# SmartCar_ESP_V2.net
KiCad netlist of a schematic drawn in EAGLE
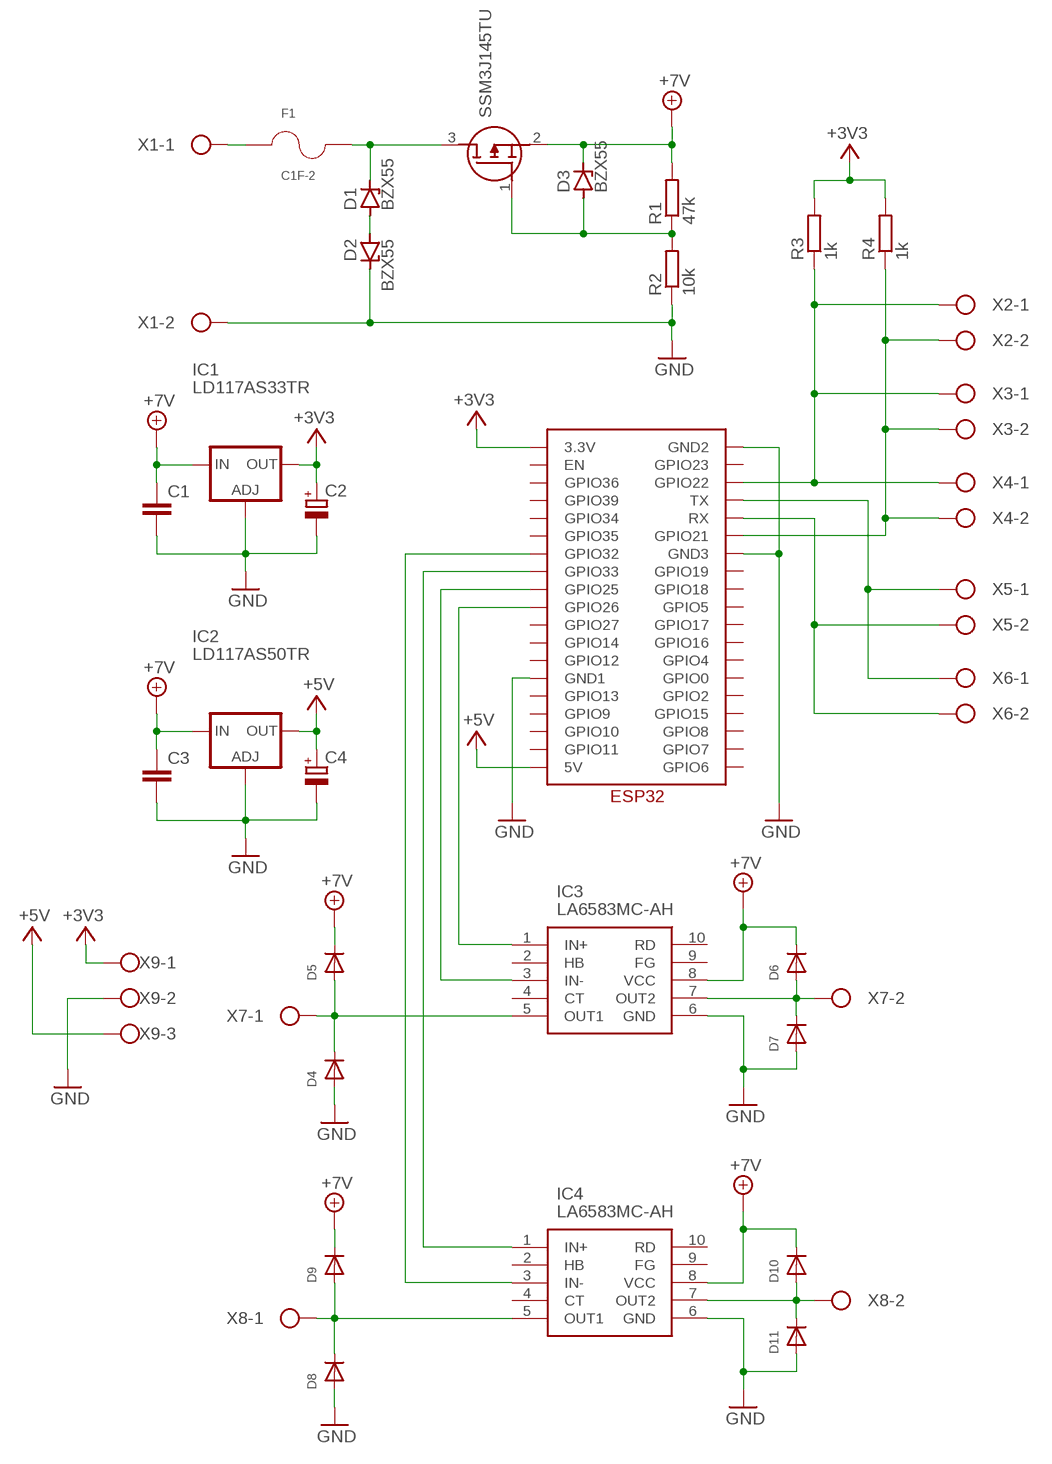
[diagram p0: schematic, sheet 1]

(export (version "E")
  (design (tool "Eeschema 10.0.6"))
  (components
    (comp (ref "C1")
      (value "C-EUC0805")
      (footprint "eagle-import:C0805")
      (libsource (lib "eagle-import") (part "C-EUC0805"))
    )
    (comp (ref "C2")
      (value "CPOL-EUE2,5-6E")
      (footprint "eagle-import:E2,5-6E")
      (libsource (lib "eagle-import") (part "CPOL-EUE2,5-6E"))
    )
    (comp (ref "C3")
      (value "C-EUC0805")
      (footprint "eagle-import:C0805")
      (libsource (lib "eagle-import") (part "C-EUC0805"))
    )
    (comp (ref "C4")
      (value "CPOL-EUE2,5-6E")
      (footprint "eagle-import:E2,5-6E")
      (libsource (lib "eagle-import") (part "CPOL-EUE2,5-6E"))
    )
    (comp (ref "D1")
      (value "BZX55")
      (footprint "eagle-import:DO35Z10")
      (libsource (lib "eagle-import") (part "BZX55"))
    )
    (comp (ref "D2")
      (value "BZX55")
      (footprint "eagle-import:DO35Z10")
      (libsource (lib "eagle-import") (part "BZX55"))
    )
    (comp (ref "D3")
      (value "BZX55")
      (footprint "eagle-import:DO35Z10")
      (libsource (lib "eagle-import") (part "BZX55"))
    )
    (comp (ref "D4")
      (value "DIODESMA")
      (footprint "eagle-import:SMADIODE")
      (libsource (lib "eagle-import") (part "DIODESMA"))
    )
    (comp (ref "D5")
      (value "DIODESMA")
      (footprint "eagle-import:SMADIODE")
      (libsource (lib "eagle-import") (part "DIODESMA"))
    )
    (comp (ref "D6")
      (value "DIODESMA")
      (footprint "eagle-import:SMADIODE")
      (libsource (lib "eagle-import") (part "DIODESMA"))
    )
    (comp (ref "D7")
      (value "DIODESMA")
      (footprint "eagle-import:SMADIODE")
      (libsource (lib "eagle-import") (part "DIODESMA"))
    )
    (comp (ref "D8")
      (value "DIODESMA")
      (footprint "eagle-import:SMADIODE")
      (libsource (lib "eagle-import") (part "DIODESMA"))
    )
    (comp (ref "D9")
      (value "DIODESMA")
      (footprint "eagle-import:SMADIODE")
      (libsource (lib "eagle-import") (part "DIODESMA"))
    )
    (comp (ref "D10")
      (value "DIODESMA")
      (footprint "eagle-import:SMADIODE")
      (libsource (lib "eagle-import") (part "DIODESMA"))
    )
    (comp (ref "D11")
      (value "DIODESMA")
      (footprint "eagle-import:SMADIODE")
      (libsource (lib "eagle-import") (part "DIODESMA"))
    )
    (comp (ref "F1")
      (value "C1F-2")
      (footprint "eagle-import:FUSC3215X83N")
      (fields (field (name "MANUFACTURER") "Bel Fuse Inc."))
      (libsource (lib "eagle-import") (part "C1F-2"))
    )
    (comp (ref "IC1")
      (value "LD117AS33TR")
      (footprint "eagle-import:SOT223")
      (libsource (lib "eagle-import") (part "LD117A?S33TR"))
    )
    (comp (ref "IC2")
      (value "LD117AS50TR")
      (footprint "eagle-import:SOT223")
      (libsource (lib "eagle-import") (part "LD117A?S50TR"))
    )
    (comp (ref "IC3")
      (value "LA6583MC-AH")
      (footprint "eagle-import:SOP100P620X155-10N")
      (fields (field (name "MOUSER_PART_NUMBER") "863-LA6583MC-AH"))
      (libsource (lib "eagle-import") (part "LA6583MC-AH"))
    )
    (comp (ref "IC4")
      (value "LA6583MC-AH")
      (footprint "eagle-import:SOP100P620X155-10N")
      (fields (field (name "MOUSER_PART_NUMBER") "863-LA6583MC-AH"))
      (libsource (lib "eagle-import") (part "LA6583MC-AH"))
    )
    (comp (ref "R1")
      (value "47k")
      (footprint "eagle-import:R0805")
      (libsource (lib "eagle-import") (part "R-EU_R0805"))
    )
    (comp (ref "R2")
      (value "10k")
      (footprint "eagle-import:R0805")
      (libsource (lib "eagle-import") (part "R-EU_R0805"))
    )
    (comp (ref "R3")
      (value "1k")
      (footprint "eagle-import:R0805")
      (libsource (lib "eagle-import") (part "R-EU_R0805"))
    )
    (comp (ref "R4")
      (value "1k")
      (footprint "eagle-import:R0805")
      (libsource (lib "eagle-import") (part "R-EU_R0805"))
    )
    (comp (ref "U$1")
      (value "ESP32")
      (footprint "eagle-import:ESP32")
      (libsource (lib "eagle-import") (part "ESP32"))
    )
    (comp (ref "U$2")
      (value "SSM3J145TU")
      (footprint "eagle-import:SOTFL65P210X75-3N")
      (libsource (lib "eagle-import") (part "SSM3J145TU"))
    )
    (comp (ref "X1")
      (value "W237-102")
      (footprint "eagle-import:W237-102")
      (fields (field (name "MPN") "237-102"))
      (libsource (lib "eagle-import") (part "W237-102"))
    )
    (comp (ref "X2")
      (value "W237-102")
      (footprint "eagle-import:W237-102")
      (fields (field (name "MPN") "237-102"))
      (libsource (lib "eagle-import") (part "W237-102"))
    )
    (comp (ref "X3")
      (value "W237-102")
      (footprint "eagle-import:W237-102")
      (fields (field (name "MPN") "237-102"))
      (libsource (lib "eagle-import") (part "W237-102"))
    )
    (comp (ref "X4")
      (value "W237-102")
      (footprint "eagle-import:W237-102")
      (fields (field (name "MPN") "237-102"))
      (libsource (lib "eagle-import") (part "W237-102"))
    )
    (comp (ref "X5")
      (value "W237-102")
      (footprint "eagle-import:W237-102")
      (fields (field (name "MPN") "237-102"))
      (libsource (lib "eagle-import") (part "W237-102"))
    )
    (comp (ref "X6")
      (value "W237-102")
      (footprint "eagle-import:W237-102")
      (fields (field (name "MPN") "237-102"))
      (libsource (lib "eagle-import") (part "W237-102"))
    )
    (comp (ref "X7")
      (value "W237-102")
      (footprint "eagle-import:W237-102")
      (fields (field (name "MPN") "237-102"))
      (libsource (lib "eagle-import") (part "W237-102"))
    )
    (comp (ref "X8")
      (value "W237-102")
      (footprint "eagle-import:W237-102")
      (fields (field (name "MPN") "237-102"))
      (libsource (lib "eagle-import") (part "W237-102"))
    )
    (comp (ref "X9")
      (value "W237-103")
      (footprint "eagle-import:W237-103")
      (fields (field (name "MPN") "237-103"))
      (libsource (lib "eagle-import") (part "W237-103"))
    )
  )
  (nets
    (net (code "1") (name "+3V3") (class "Default")
      (node (ref "C2") (pin "+") (pinfunction "+_+") (pintype "passive"))
      (node (ref "IC1") (pin "4") (pinfunction "OUT_4") (pintype "passive"))
      (node (ref "R3") (pin "2") (pinfunction "2_2") (pintype "passive"))
      (node (ref "R4") (pin "2") (pinfunction "2_2") (pintype "passive"))
      (node (ref "U$1") (pin "3.3V") (pinfunction "3.3V_3.3V") (pintype "bidirectional"))
      (node (ref "X9") (pin "1") (pinfunction "KL_1") (pintype "passive"))
    )
    (net (code "2") (name "+5V") (class "Default")
      (node (ref "C4") (pin "+") (pinfunction "+_+") (pintype "passive"))
      (node (ref "IC2") (pin "4") (pinfunction "OUT_4") (pintype "passive"))
      (node (ref "U$1") (pin "5V") (pinfunction "5V_5V") (pintype "bidirectional"))
      (node (ref "X9") (pin "3") (pinfunction "KL_3") (pintype "passive"))
    )
    (net (code "3") (name "+7V") (class "Default")
      (node (ref "C1") (pin "1") (pinfunction "1_1") (pintype "passive"))
      (node (ref "C3") (pin "1") (pinfunction "1_1") (pintype "passive"))
      (node (ref "D10") (pin "C") (pinfunction "C_C") (pintype "passive"))
      (node (ref "D3") (pin "C") (pinfunction "C_C") (pintype "passive"))
      (node (ref "D5") (pin "C") (pinfunction "C_C") (pintype "passive"))
      (node (ref "D6") (pin "C") (pinfunction "C_C") (pintype "passive"))
      (node (ref "D9") (pin "C") (pinfunction "C_C") (pintype "passive"))
      (node (ref "IC1") (pin "3") (pinfunction "IN_3") (pintype "input"))
      (node (ref "IC2") (pin "3") (pinfunction "IN_3") (pintype "input"))
      (node (ref "IC3") (pin "8") (pinfunction "VCC_8") (pintype "bidirectional"))
      (node (ref "IC4") (pin "8") (pinfunction "VCC_8") (pintype "bidirectional"))
      (node (ref "R1") (pin "2") (pinfunction "2_2") (pintype "passive"))
      (node (ref "U$2") (pin "2") (pinfunction "S_2") (pintype "bidirectional"))
    )
    (net (code "4") (name "GND") (class "Default")
      (node (ref "C1") (pin "2") (pinfunction "2_2") (pintype "passive"))
      (node (ref "C2") (pin "-") (pinfunction "-_-") (pintype "passive"))
      (node (ref "C3") (pin "2") (pinfunction "2_2") (pintype "passive"))
      (node (ref "C4") (pin "-") (pinfunction "-_-") (pintype "passive"))
      (node (ref "D11") (pin "A") (pinfunction "A_A") (pintype "passive"))
      (node (ref "D2") (pin "C") (pinfunction "C_C") (pintype "passive"))
      (node (ref "D4") (pin "A") (pinfunction "A_A") (pintype "passive"))
      (node (ref "D7") (pin "A") (pinfunction "A_A") (pintype "passive"))
      (node (ref "D8") (pin "A") (pinfunction "A_A") (pintype "passive"))
      (node (ref "IC1") (pin "1") (pinfunction "ADJ_1") (pintype "input"))
      (node (ref "IC2") (pin "1") (pinfunction "ADJ_1") (pintype "input"))
      (node (ref "IC3") (pin "6") (pinfunction "GND_6") (pintype "output"))
      (node (ref "IC4") (pin "6") (pinfunction "GND_6") (pintype "output"))
      (node (ref "R2") (pin "1") (pinfunction "1_1") (pintype "passive"))
      (node (ref "U$1") (pin "GND1") (pinfunction "GND1_GND1") (pintype "bidirectional"))
      (node (ref "U$1") (pin "GND2") (pinfunction "GND2_GND2") (pintype "bidirectional"))
      (node (ref "U$1") (pin "GND3") (pinfunction "GND3_GND3") (pintype "bidirectional"))
      (node (ref "X1") (pin "2") (pinfunction "KL_2") (pintype "passive"))
      (node (ref "X9") (pin "2") (pinfunction "KL_2") (pintype "passive"))
    )
    (net (code "5") (name "Net-(D1-PadA)") (class "Default")
      (node (ref "D1") (pin "A") (pinfunction "A_A") (pintype "passive"))
      (node (ref "D2") (pin "A") (pinfunction "A_A") (pintype "passive"))
    )
    (net (code "6") (name "Net-(IC3-IN+)") (class "Default")
      (node (ref "IC3") (pin "1") (pinfunction "IN+_1") (pintype "input"))
      (node (ref "U$1") (pin "GPIO26") (pinfunction "GPIO26_GPIO26") (pintype "bidirectional"))
    )
    (net (code "7") (name "Net-(IC3-IN-)") (class "Default")
      (node (ref "IC3") (pin "3") (pinfunction "IN-_3") (pintype "bidirectional"))
      (node (ref "U$1") (pin "GPIO25") (pinfunction "GPIO25_GPIO25") (pintype "bidirectional"))
    )
    (net (code "8") (name "Net-(IC3-OUT1)") (class "Default")
      (node (ref "D4") (pin "C") (pinfunction "C_C") (pintype "passive"))
      (node (ref "D5") (pin "A") (pinfunction "A_A") (pintype "passive"))
      (node (ref "IC3") (pin "5") (pinfunction "OUT1_5") (pintype "power_in"))
      (node (ref "X7") (pin "1") (pinfunction "KL_1") (pintype "passive"))
    )
    (net (code "9") (name "Net-(IC3-OUT2)") (class "Default")
      (node (ref "D6") (pin "A") (pinfunction "A_A") (pintype "passive"))
      (node (ref "D7") (pin "C") (pinfunction "C_C") (pintype "passive"))
      (node (ref "IC3") (pin "7") (pinfunction "OUT2_7") (pintype "power_in"))
      (node (ref "X7") (pin "2") (pinfunction "KL_2") (pintype "passive"))
    )
    (net (code "10") (name "Net-(IC4-IN+)") (class "Default")
      (node (ref "IC4") (pin "1") (pinfunction "IN+_1") (pintype "input"))
      (node (ref "U$1") (pin "GPIO33") (pinfunction "GPIO33_GPIO33") (pintype "bidirectional"))
    )
    (net (code "11") (name "Net-(IC4-IN-)") (class "Default")
      (node (ref "IC4") (pin "3") (pinfunction "IN-_3") (pintype "bidirectional"))
      (node (ref "U$1") (pin "GPIO32") (pinfunction "GPIO32_GPIO32") (pintype "bidirectional"))
    )
    (net (code "12") (name "Net-(IC4-OUT1)") (class "Default")
      (node (ref "D8") (pin "C") (pinfunction "C_C") (pintype "passive"))
      (node (ref "D9") (pin "A") (pinfunction "A_A") (pintype "passive"))
      (node (ref "IC4") (pin "5") (pinfunction "OUT1_5") (pintype "power_in"))
      (node (ref "X8") (pin "1") (pinfunction "KL_1") (pintype "passive"))
    )
    (net (code "13") (name "Net-(IC4-OUT2)") (class "Default")
      (node (ref "D10") (pin "A") (pinfunction "A_A") (pintype "passive"))
      (node (ref "D11") (pin "C") (pinfunction "C_C") (pintype "passive"))
      (node (ref "IC4") (pin "7") (pinfunction "OUT2_7") (pintype "power_in"))
      (node (ref "X8") (pin "2") (pinfunction "KL_2") (pintype "passive"))
    )
    (net (code "14") (name "Net-(U$2-D)") (class "Default")
      (node (ref "D1") (pin "C") (pinfunction "C_C") (pintype "passive"))
      (node (ref "F1") (pin "2") (pinfunction "2_2") (pintype "passive"))
      (node (ref "U$2") (pin "3") (pinfunction "D_3") (pintype "bidirectional"))
    )
    (net (code "15") (name "Net-(U$2-G)") (class "Default")
      (node (ref "D3") (pin "A") (pinfunction "A_A") (pintype "passive"))
      (node (ref "R1") (pin "1") (pinfunction "1_1") (pintype "passive"))
      (node (ref "R2") (pin "2") (pinfunction "2_2") (pintype "passive"))
      (node (ref "U$2") (pin "1") (pinfunction "G_1") (pintype "bidirectional"))
    )
    (net (code "16") (name "Net-(X1A-KL)") (class "Default")
      (node (ref "F1") (pin "1") (pinfunction "1_1") (pintype "passive"))
      (node (ref "X1") (pin "1") (pinfunction "KL_1") (pintype "passive"))
    )
    (net (code "17") (name "Net-(X2A-KL)") (class "Default")
      (node (ref "R3") (pin "1") (pinfunction "1_1") (pintype "passive"))
      (node (ref "U$1") (pin "GPIO22") (pinfunction "GPIO22_GPIO22") (pintype "bidirectional"))
      (node (ref "X2") (pin "1") (pinfunction "KL_1") (pintype "passive"))
      (node (ref "X3") (pin "1") (pinfunction "KL_1") (pintype "passive"))
      (node (ref "X4") (pin "1") (pinfunction "KL_1") (pintype "passive"))
    )
    (net (code "18") (name "Net-(X2B-KL)") (class "Default")
      (node (ref "R4") (pin "1") (pinfunction "1_1") (pintype "passive"))
      (node (ref "U$1") (pin "GPIO21") (pinfunction "GPIO21_GPIO21") (pintype "bidirectional"))
      (node (ref "X2") (pin "2") (pinfunction "KL_2") (pintype "passive"))
      (node (ref "X3") (pin "2") (pinfunction "KL_2") (pintype "passive"))
      (node (ref "X4") (pin "2") (pinfunction "KL_2") (pintype "passive"))
    )
    (net (code "19") (name "Net-(X5A-KL)") (class "Default")
      (node (ref "U$1") (pin "TX") (pinfunction "TX_TX") (pintype "bidirectional"))
      (node (ref "X5") (pin "1") (pinfunction "KL_1") (pintype "passive"))
      (node (ref "X6") (pin "1") (pinfunction "KL_1") (pintype "passive"))
    )
    (net (code "20") (name "Net-(X5B-KL)") (class "Default")
      (node (ref "U$1") (pin "RX") (pinfunction "RX_RX") (pintype "bidirectional"))
      (node (ref "X5") (pin "2") (pinfunction "KL_2") (pintype "passive"))
      (node (ref "X6") (pin "2") (pinfunction "KL_2") (pintype "passive"))
    )
    (net (code "21") (name "unconnected-(IC3-CT-Pad4)") (class "Default")
      (node (ref "IC3") (pin "4") (pinfunction "CT_4") (pintype "output"))
    )
    (net (code "22") (name "unconnected-(IC3-FG-Pad9)") (class "Default")
      (node (ref "IC3") (pin "9") (pinfunction "FG_9") (pintype "bidirectional"))
    )
    (net (code "23") (name "unconnected-(IC3-HB-Pad2)") (class "Default")
      (node (ref "IC3") (pin "2") (pinfunction "HB_2") (pintype "input"))
    )
    (net (code "24") (name "unconnected-(IC3-RD-Pad10)") (class "Default")
      (node (ref "IC3") (pin "10") (pinfunction "RD_10") (pintype "bidirectional"))
    )
    (net (code "25") (name "unconnected-(IC4-CT-Pad4)") (class "Default")
      (node (ref "IC4") (pin "4") (pinfunction "CT_4") (pintype "output"))
    )
    (net (code "26") (name "unconnected-(IC4-FG-Pad9)") (class "Default")
      (node (ref "IC4") (pin "9") (pinfunction "FG_9") (pintype "bidirectional"))
    )
    (net (code "27") (name "unconnected-(IC4-HB-Pad2)") (class "Default")
      (node (ref "IC4") (pin "2") (pinfunction "HB_2") (pintype "input"))
    )
    (net (code "28") (name "unconnected-(IC4-RD-Pad10)") (class "Default")
      (node (ref "IC4") (pin "10") (pinfunction "RD_10") (pintype "bidirectional"))
    )
    (net (code "29") (name "unconnected-(U$1-PadEN)") (class "Default")
      (node (ref "U$1") (pin "EN") (pinfunction "EN_EN") (pintype "bidirectional"))
    )
    (net (code "30") (name "unconnected-(U$1-PadGPIO0)") (class "Default")
      (node (ref "U$1") (pin "GPIO0") (pinfunction "GPIO0_GPIO0") (pintype "bidirectional"))
    )
    (net (code "31") (name "unconnected-(U$1-PadGPIO2)") (class "Default")
      (node (ref "U$1") (pin "GPIO2") (pinfunction "GPIO2_GPIO2") (pintype "bidirectional"))
    )
    (net (code "32") (name "unconnected-(U$1-PadGPIO4)") (class "Default")
      (node (ref "U$1") (pin "GPIO4") (pinfunction "GPIO4_GPIO4") (pintype "bidirectional"))
    )
    (net (code "33") (name "unconnected-(U$1-PadGPIO5)") (class "Default")
      (node (ref "U$1") (pin "GPIO5") (pinfunction "GPIO5_GPIO5") (pintype "bidirectional"))
    )
    (net (code "34") (name "unconnected-(U$1-PadGPIO6)") (class "Default")
      (node (ref "U$1") (pin "GPIO6") (pinfunction "GPIO6_GPIO6") (pintype "bidirectional"))
    )
    (net (code "35") (name "unconnected-(U$1-PadGPIO7)") (class "Default")
      (node (ref "U$1") (pin "GPIO7") (pinfunction "GPIO7_GPIO7") (pintype "bidirectional"))
    )
    (net (code "36") (name "unconnected-(U$1-PadGPIO8)") (class "Default")
      (node (ref "U$1") (pin "GPIO8") (pinfunction "GPIO8_GPIO8") (pintype "bidirectional"))
    )
    (net (code "37") (name "unconnected-(U$1-PadGPIO9)") (class "Default")
      (node (ref "U$1") (pin "GPIO9") (pinfunction "GPIO9_GPIO9") (pintype "bidirectional"))
    )
    (net (code "38") (name "unconnected-(U$1-PadGPIO10)") (class "Default")
      (node (ref "U$1") (pin "GPIO10") (pinfunction "GPIO10_GPIO10") (pintype "bidirectional"))
    )
    (net (code "39") (name "unconnected-(U$1-PadGPIO11)") (class "Default")
      (node (ref "U$1") (pin "GPIO11") (pinfunction "GPIO11_GPIO11") (pintype "bidirectional"))
    )
    (net (code "40") (name "unconnected-(U$1-PadGPIO12)") (class "Default")
      (node (ref "U$1") (pin "GPIO12") (pinfunction "GPIO12_GPIO12") (pintype "bidirectional"))
    )
    (net (code "41") (name "unconnected-(U$1-PadGPIO13)") (class "Default")
      (node (ref "U$1") (pin "GPIO13") (pinfunction "GPIO13_GPIO13") (pintype "bidirectional"))
    )
    (net (code "42") (name "unconnected-(U$1-PadGPIO14)") (class "Default")
      (node (ref "U$1") (pin "GPIO14") (pinfunction "GPIO14_GPIO14") (pintype "bidirectional"))
    )
    (net (code "43") (name "unconnected-(U$1-PadGPIO15)") (class "Default")
      (node (ref "U$1") (pin "GPIO15") (pinfunction "GPIO15_GPIO15") (pintype "bidirectional"))
    )
    (net (code "44") (name "unconnected-(U$1-PadGPIO16)") (class "Default")
      (node (ref "U$1") (pin "GPIO16") (pinfunction "GPIO16_GPIO16") (pintype "bidirectional"))
    )
    (net (code "45") (name "unconnected-(U$1-PadGPIO17)") (class "Default")
      (node (ref "U$1") (pin "GPIO17") (pinfunction "GPIO17_GPIO17") (pintype "bidirectional"))
    )
    (net (code "46") (name "unconnected-(U$1-PadGPIO18)") (class "Default")
      (node (ref "U$1") (pin "GPIO18") (pinfunction "GPIO18_GPIO18") (pintype "bidirectional"))
    )
    (net (code "47") (name "unconnected-(U$1-PadGPIO19)") (class "Default")
      (node (ref "U$1") (pin "GPIO19") (pinfunction "GPIO19_GPIO19") (pintype "bidirectional"))
    )
    (net (code "48") (name "unconnected-(U$1-PadGPIO23)") (class "Default")
      (node (ref "U$1") (pin "GPIO23") (pinfunction "GPIO23_GPIO23") (pintype "bidirectional"))
    )
    (net (code "49") (name "unconnected-(U$1-PadGPIO27)") (class "Default")
      (node (ref "U$1") (pin "GPIO27") (pinfunction "GPIO27_GPIO27") (pintype "bidirectional"))
    )
    (net (code "50") (name "unconnected-(U$1-PadGPIO34)") (class "Default")
      (node (ref "U$1") (pin "GPIO34") (pinfunction "GPIO34_GPIO34") (pintype "bidirectional"))
    )
    (net (code "51") (name "unconnected-(U$1-PadGPIO35)") (class "Default")
      (node (ref "U$1") (pin "GPIO35") (pinfunction "GPIO35_GPIO35") (pintype "bidirectional"))
    )
    (net (code "52") (name "unconnected-(U$1-PadGPIO36)") (class "Default")
      (node (ref "U$1") (pin "GPIO36") (pinfunction "GPIO36_GPIO36") (pintype "bidirectional"))
    )
    (net (code "53") (name "unconnected-(U$1-PadGPIO39)") (class "Default")
      (node (ref "U$1") (pin "GPIO39") (pinfunction "GPIO39_GPIO39") (pintype "bidirectional"))
    )
  )
)
